# DAC_STM32_Board_v4_1_-_AD5391.net
KiCad netlist of a schematic drawn in EAGLE
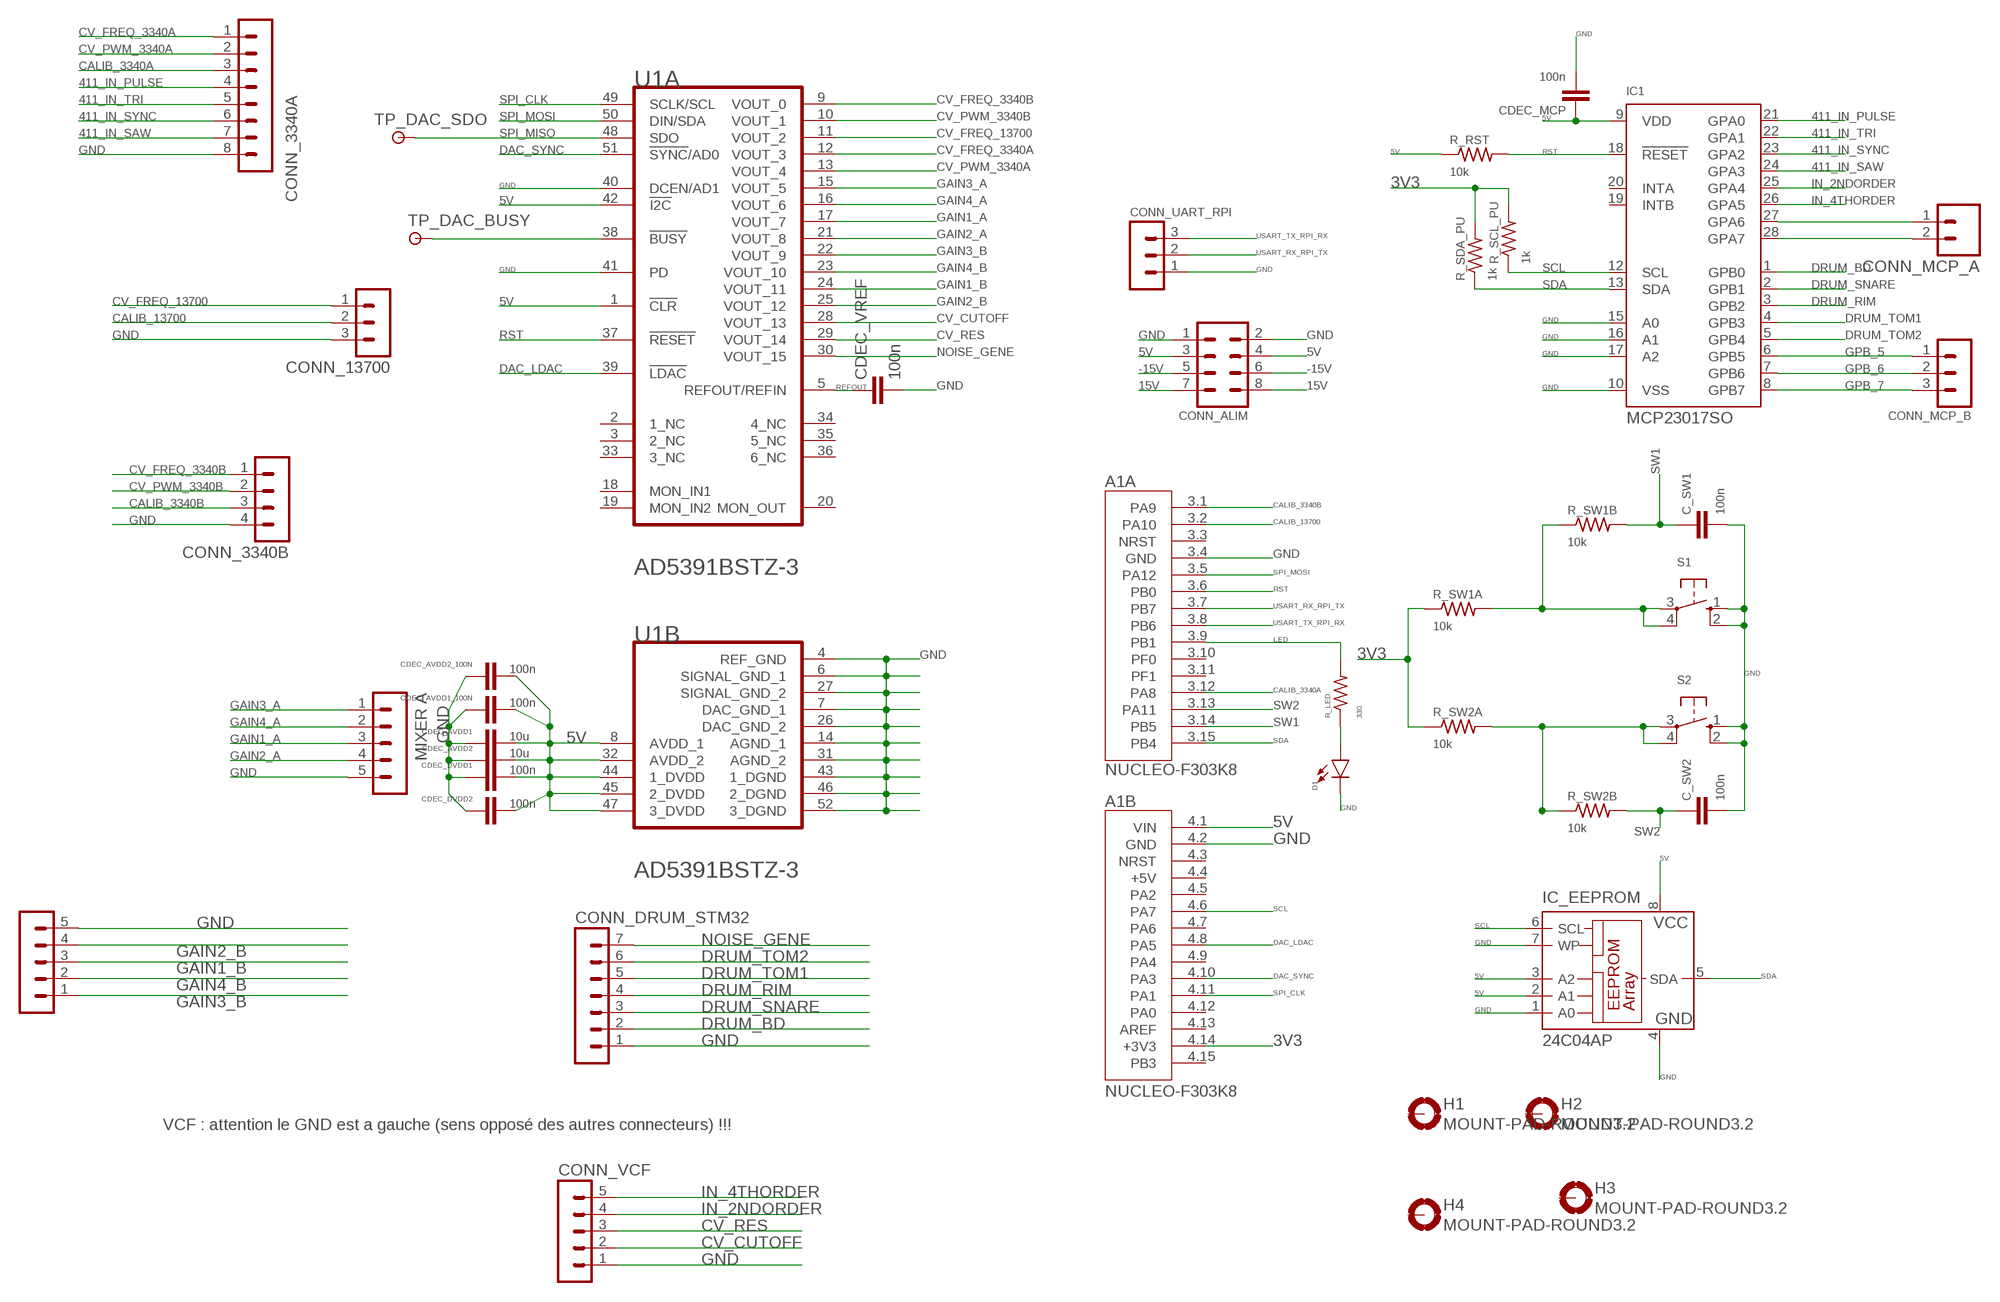
[diagram p0: schematic, sheet 1]

(export (version "E")
  (design (tool "Eeschema 10.0.6"))
  (components
    (comp (ref "A1")
      (value "NUCLEO-F303K8")
      (footprint "eagle-import:MODULE_NUCLEO-F303K8")
      (fields (field (name "DIGI-KEY_PART_NUMBER") "497-15981-ND") (field (name "MF") "STMicroelectronics"))
      (libsource (lib "eagle-import") (part "NUCLEO-F303K8"))
    )
    (comp (ref "CDEC_AVDD1")
      (value "10u")
      (footprint "eagle-import:C050-030X075")
      (libsource (lib "eagle-import") (part "C-EU050-030X075"))
    )
    (comp (ref "CDEC_AVDD1_100N")
      (value "100n")
      (footprint "eagle-import:C050-030X075")
      (libsource (lib "eagle-import") (part "C-EU050-030X075"))
    )
    (comp (ref "CDEC_AVDD2")
      (value "10u")
      (footprint "eagle-import:C050-030X075")
      (libsource (lib "eagle-import") (part "C-EU050-030X075"))
    )
    (comp (ref "CDEC_AVDD2_100N")
      (value "100n")
      (footprint "eagle-import:C050-030X075")
      (libsource (lib "eagle-import") (part "C-EU050-030X075"))
    )
    (comp (ref "CDEC_DVDD1")
      (value "100n")
      (footprint "eagle-import:C075-032X103")
      (libsource (lib "eagle-import") (part "C-EU075-032X103"))
    )
    (comp (ref "CDEC_DVDD2")
      (value "100n")
      (footprint "eagle-import:C050-030X075")
      (libsource (lib "eagle-import") (part "C-EU050-030X075"))
    )
    (comp (ref "CDEC_MCP")
      (value "100n")
      (footprint "eagle-import:C075-032X103")
      (libsource (lib "eagle-import") (part "C-EU075-032X103"))
    )
    (comp (ref "CDEC_VREF")
      (value "100n")
      (footprint "eagle-import:C050-030X075")
      (libsource (lib "eagle-import") (part "C-EU050-030X075"))
    )
    (comp (ref "CONN_3340A")
      (value "MA08-1")
      (footprint "eagle-import:MA08-1")
      (libsource (lib "eagle-import") (part "MA08-1"))
    )
    (comp (ref "CONN_3340B")
      (value "MA04-1")
      (footprint "eagle-import:MA04-1")
      (libsource (lib "eagle-import") (part "MA04-1"))
    )
    (comp (ref "CONN_13700")
      (value "MA03-1")
      (footprint "eagle-import:MA03-1")
      (libsource (lib "eagle-import") (part "MA03-1"))
    )
    (comp (ref "CONN_ALIM")
      (value "MA04-2")
      (footprint "eagle-import:MA04-2")
      (libsource (lib "eagle-import") (part "MA04-2"))
    )
    (comp (ref "CONN_DRUM_STM32")
      (value "MA07-1")
      (footprint "eagle-import:MA07-1")
      (libsource (lib "eagle-import") (part "MA07-1"))
    )
    (comp (ref "CONN_MCP_A")
      (value "M02")
      (footprint "eagle-import:02P")
      (libsource (lib "eagle-import") (part "M02"))
    )
    (comp (ref "CONN_MCP_B")
      (value "MA03-1")
      (footprint "eagle-import:MA03-1")
      (libsource (lib "eagle-import") (part "MA03-1"))
    )
    (comp (ref "CONN_MIX_A")
      (value "MA05-1")
      (footprint "eagle-import:MA05-1")
      (libsource (lib "eagle-import") (part "MA05-1"))
    )
    (comp (ref "CONN_MIX_B")
      (value "MA05-1")
      (footprint "eagle-import:MA05-1")
      (libsource (lib "eagle-import") (part "MA05-1"))
    )
    (comp (ref "CONN_UART_RPI")
      (value "MA03-1")
      (footprint "eagle-import:MA03-1")
      (libsource (lib "eagle-import") (part "MA03-1"))
    )
    (comp (ref "CONN_VCF")
      (value "MA05-1")
      (footprint "eagle-import:MA05-1")
      (libsource (lib "eagle-import") (part "MA05-1"))
    )
    (comp (ref "C_SW1")
      (value "100n")
      (footprint "eagle-import:C050-030X075")
      (libsource (lib "eagle-import") (part "C-EU050-030X075"))
    )
    (comp (ref "C_SW2")
      (value "100n")
      (footprint "eagle-import:C050-030X075")
      (libsource (lib "eagle-import") (part "C-EU050-030X075"))
    )
    (comp (ref "D1")
      (value "LED-3MM-NO_SILK")
      (footprint "eagle-import:LED_3MM-NS")
      (libsource (lib "eagle-import") (part "LED-3MM-NO_SILK"))
    )
    (comp (ref "H1")
      (value "MOUNT-PAD-ROUND3.2")
      (footprint "eagle-import:3,2-PAD")
      (libsource (lib "eagle-import") (part "MOUNT-PAD-ROUND3.2"))
    )
    (comp (ref "H2")
      (value "MOUNT-PAD-ROUND3.2")
      (footprint "eagle-import:3,2-PAD")
      (libsource (lib "eagle-import") (part "MOUNT-PAD-ROUND3.2"))
    )
    (comp (ref "H3")
      (value "MOUNT-PAD-ROUND3.2")
      (footprint "eagle-import:3,2-PAD")
      (libsource (lib "eagle-import") (part "MOUNT-PAD-ROUND3.2"))
    )
    (comp (ref "H4")
      (value "MOUNT-PAD-ROUND3.2")
      (footprint "eagle-import:3,2-PAD")
      (libsource (lib "eagle-import") (part "MOUNT-PAD-ROUND3.2"))
    )
    (comp (ref "IC1")
      (value "MCP23017SO")
      (footprint "eagle-import:SO28W")
      (fields (field (name "MF") "MICROCHIP") (field (name "MPN") "MCP23017-E/SO"))
      (libsource (lib "eagle-import") (part "MCP23017SO"))
    )
    (comp (ref "IC_EEPROM")
      (value "24C04AP")
      (footprint "eagle-import:DIL8")
      (fields (field (name "MPN") "AT24C04B-PU"))
      (libsource (lib "eagle-import") (part "24CP04A"))
    )
    (comp (ref "R_LED")
      (value "330")
      (footprint "eagle-import:0204_7")
      (libsource (lib "eagle-import") (part "R-US_0204/7"))
    )
    (comp (ref "R_RST")
      (value "10k")
      (footprint "eagle-import:0207_10")
      (libsource (lib "eagle-import") (part "R-US_0207/10"))
    )
    (comp (ref "R_SCL_PU")
      (value "1k")
      (footprint "eagle-import:0207_10")
      (libsource (lib "eagle-import") (part "R-US_0207/10"))
    )
    (comp (ref "R_SDA_PU")
      (value "1k")
      (footprint "eagle-import:0207_10")
      (libsource (lib "eagle-import") (part "R-US_0207/10"))
    )
    (comp (ref "R_SW1A")
      (value "10k")
      (footprint "eagle-import:0207_10")
      (libsource (lib "eagle-import") (part "R-US_0207/10"))
    )
    (comp (ref "R_SW1B")
      (value "10k")
      (footprint "eagle-import:0207_10")
      (libsource (lib "eagle-import") (part "R-US_0207/10"))
    )
    (comp (ref "R_SW2A")
      (value "10k")
      (footprint "eagle-import:0207_10")
      (libsource (lib "eagle-import") (part "R-US_0207/10"))
    )
    (comp (ref "R_SW2B")
      (value "10k")
      (footprint "eagle-import:0207_10")
      (libsource (lib "eagle-import") (part "R-US_0207/10"))
    )
    (comp (ref "S1")
      (value "10-XX")
      (footprint "eagle-import:B3F-10XX")
      (fields (field (name "MPN") "B3F-1000"))
      (libsource (lib "eagle-import") (part "10-XX"))
    )
    (comp (ref "S2")
      (value "10-XX")
      (footprint "eagle-import:B3F-10XX")
      (fields (field (name "MPN") "B3F-1000"))
      (libsource (lib "eagle-import") (part "10-XX"))
    )
    (comp (ref "TP_DAC_BUSY")
      (value "PAD-TESTPOINT")
      (footprint "eagle-import:1,6_0,8")
      (libsource (lib "eagle-import") (part "PAD-TESTPOINT"))
    )
    (comp (ref "TP_DAC_SDO")
      (value "PAD-TESTPOINT")
      (footprint "eagle-import:1,6_0,8")
      (libsource (lib "eagle-import") (part "PAD-TESTPOINT"))
    )
    (comp (ref "U1")
      (value "ANALOG_DEVICES_AD5391BSTZ-3ANALOG_DEVICES_AD5391BSTZ-3_0_0")
      (footprint "eagle-import:ANALOG_DEVICES_AD5391BSTZ-3_0")
      (fields (field (name "MF") "Analog Devices") (field (name "MPN") "AD5391BSTZ-3"))
      (libsource (lib "eagle-import") (part "ANALOG_DEVICES_AD5391BSTZ-3ANALOG_DEVICES_AD5391BSTZ-3_0_0"))
    )
  )
  (nets
    (net (code "1") (name "/-15V") (class "Default")
      (node (ref "CONN_ALIM") (pin "5") (pinfunction "5_5") (pintype "passive"))
      (node (ref "CONN_ALIM") (pin "6") (pinfunction "6_6") (pintype "passive"))
    )
    (net (code "2") (name "/3V3") (class "Default")
      (node (ref "A1") (pin "4.14") (pinfunction "+3V3_4.14") (pintype "bidirectional"))
      (node (ref "R_SCL_PU") (pin "2") (pinfunction "2_2") (pintype "passive"))
      (node (ref "R_SDA_PU") (pin "2") (pinfunction "2_2") (pintype "passive"))
      (node (ref "R_SW1A") (pin "1") (pinfunction "1_1") (pintype "passive"))
      (node (ref "R_SW2A") (pin "1") (pinfunction "1_1") (pintype "passive"))
    )
    (net (code "3") (name "/5V") (class "Default")
      (node (ref "A1") (pin "4.1") (pinfunction "VIN_4.1") (pintype "bidirectional"))
      (node (ref "CDEC_AVDD1") (pin "2") (pinfunction "2_2") (pintype "passive"))
      (node (ref "CDEC_AVDD1_100N") (pin "2") (pinfunction "2_2") (pintype "passive"))
      (node (ref "CDEC_AVDD2") (pin "2") (pinfunction "2_2") (pintype "passive"))
      (node (ref "CDEC_AVDD2_100N") (pin "2") (pinfunction "2_2") (pintype "passive"))
      (node (ref "CDEC_DVDD1") (pin "2") (pinfunction "2_2") (pintype "passive"))
      (node (ref "CDEC_DVDD2") (pin "2") (pinfunction "2_2") (pintype "passive"))
      (node (ref "CDEC_MCP") (pin "1") (pinfunction "1_1") (pintype "passive"))
      (node (ref "CONN_ALIM") (pin "3") (pinfunction "3_3") (pintype "passive"))
      (node (ref "CONN_ALIM") (pin "4") (pinfunction "4_4") (pintype "passive"))
      (node (ref "IC1") (pin "9") (pinfunction "VDD_9") (pintype "power_in"))
      (node (ref "IC_EEPROM") (pin "2") (pinfunction "A1_2") (pintype "input"))
      (node (ref "IC_EEPROM") (pin "3") (pinfunction "A2_3") (pintype "input"))
      (node (ref "IC_EEPROM") (pin "8") (pinfunction "VCC_8") (pintype "power_in"))
      (node (ref "R_RST") (pin "1") (pinfunction "1_1") (pintype "passive"))
      (node (ref "U1") (pin "1") (pinfunction "~{CLR}_1") (pintype "input"))
      (node (ref "U1") (pin "32") (pinfunction "AVDD_2_32") (pintype "power_in"))
      (node (ref "U1") (pin "42") (pinfunction "~{I2C}_42") (pintype "input"))
      (node (ref "U1") (pin "44") (pinfunction "1_DVDD_44") (pintype "power_in"))
      (node (ref "U1") (pin "45") (pinfunction "2_DVDD_45") (pintype "power_in"))
      (node (ref "U1") (pin "47") (pinfunction "3_DVDD_47") (pintype "power_in"))
      (node (ref "U1") (pin "8") (pinfunction "AVDD_1_8") (pintype "power_in"))
    )
    (net (code "4") (name "/15V") (class "Default")
      (node (ref "CONN_ALIM") (pin "7") (pinfunction "7_7") (pintype "passive"))
      (node (ref "CONN_ALIM") (pin "8") (pinfunction "8_8") (pintype "passive"))
    )
    (net (code "5") (name "/411_IN_PULSE") (class "Default")
      (node (ref "CONN_3340A") (pin "4") (pinfunction "4_4") (pintype "passive"))
      (node (ref "IC1") (pin "21") (pinfunction "GPA0_21") (pintype "bidirectional"))
    )
    (net (code "6") (name "/411_IN_SAW") (class "Default")
      (node (ref "CONN_3340A") (pin "7") (pinfunction "7_7") (pintype "passive"))
      (node (ref "IC1") (pin "24") (pinfunction "GPA3_24") (pintype "bidirectional"))
    )
    (net (code "7") (name "/411_IN_SYNC") (class "Default")
      (node (ref "CONN_3340A") (pin "6") (pinfunction "6_6") (pintype "passive"))
      (node (ref "IC1") (pin "23") (pinfunction "GPA2_23") (pintype "bidirectional"))
    )
    (net (code "8") (name "/411_IN_TRI") (class "Default")
      (node (ref "CONN_3340A") (pin "5") (pinfunction "5_5") (pintype "passive"))
      (node (ref "IC1") (pin "22") (pinfunction "GPA1_22") (pintype "bidirectional"))
    )
    (net (code "9") (name "/CALIB_3340A") (class "Default")
      (node (ref "A1") (pin "3.12") (pinfunction "PA8_3.12") (pintype "bidirectional"))
      (node (ref "CONN_3340A") (pin "3") (pinfunction "3_3") (pintype "passive"))
    )
    (net (code "10") (name "/CALIB_3340B") (class "Default")
      (node (ref "A1") (pin "3.1") (pinfunction "PA9_3.1") (pintype "bidirectional"))
      (node (ref "CONN_3340B") (pin "3") (pinfunction "3_3") (pintype "passive"))
    )
    (net (code "11") (name "/CALIB_13700") (class "Default")
      (node (ref "A1") (pin "3.2") (pinfunction "PA10_3.2") (pintype "bidirectional"))
      (node (ref "CONN_13700") (pin "2") (pinfunction "2_2") (pintype "passive"))
    )
    (net (code "12") (name "/CV_CUTOFF") (class "Default")
      (node (ref "CONN_VCF") (pin "2") (pinfunction "2_2") (pintype "passive"))
      (node (ref "U1") (pin "28") (pinfunction "VOUT_13_28") (pintype "tri_state"))
    )
    (net (code "13") (name "/CV_FREQ_3340A") (class "Default")
      (node (ref "CONN_3340A") (pin "1") (pinfunction "1_1") (pintype "passive"))
      (node (ref "U1") (pin "12") (pinfunction "VOUT_3_12") (pintype "tri_state"))
    )
    (net (code "14") (name "/CV_FREQ_3340B") (class "Default")
      (node (ref "CONN_3340B") (pin "1") (pinfunction "1_1") (pintype "passive"))
      (node (ref "U1") (pin "9") (pinfunction "VOUT_0_9") (pintype "tri_state"))
    )
    (net (code "15") (name "/CV_FREQ_13700") (class "Default")
      (node (ref "CONN_13700") (pin "1") (pinfunction "1_1") (pintype "passive"))
      (node (ref "U1") (pin "11") (pinfunction "VOUT_2_11") (pintype "tri_state"))
    )
    (net (code "16") (name "/CV_PWM_3340A") (class "Default")
      (node (ref "CONN_3340A") (pin "2") (pinfunction "2_2") (pintype "passive"))
      (node (ref "U1") (pin "13") (pinfunction "VOUT_4_13") (pintype "tri_state"))
    )
    (net (code "17") (name "/CV_PWM_3340B") (class "Default")
      (node (ref "CONN_3340B") (pin "2") (pinfunction "2_2") (pintype "passive"))
      (node (ref "U1") (pin "10") (pinfunction "VOUT_1_10") (pintype "tri_state"))
    )
    (net (code "18") (name "/CV_RES") (class "Default")
      (node (ref "CONN_VCF") (pin "3") (pinfunction "3_3") (pintype "passive"))
      (node (ref "U1") (pin "29") (pinfunction "VOUT_14_29") (pintype "tri_state"))
    )
    (net (code "19") (name "/DAC_LDAC") (class "Default")
      (node (ref "A1") (pin "4.8") (pinfunction "PA5_4.8") (pintype "bidirectional"))
      (node (ref "U1") (pin "39") (pinfunction "~{LDAC}_39") (pintype "input"))
    )
    (net (code "20") (name "/DAC_SYNC") (class "Default")
      (node (ref "A1") (pin "4.10") (pinfunction "PA3_4.10") (pintype "bidirectional"))
      (node (ref "U1") (pin "51") (pinfunction "~{SYNC}/AD0_51") (pintype "input"))
    )
    (net (code "21") (name "/DRUM_BD") (class "Default")
      (node (ref "CONN_DRUM_STM32") (pin "2") (pinfunction "2_2") (pintype "passive"))
      (node (ref "IC1") (pin "1") (pinfunction "GPB0_1") (pintype "bidirectional"))
    )
    (net (code "22") (name "/DRUM_RIM") (class "Default")
      (node (ref "CONN_DRUM_STM32") (pin "4") (pinfunction "4_4") (pintype "passive"))
      (node (ref "IC1") (pin "3") (pinfunction "GPB2_3") (pintype "bidirectional"))
    )
    (net (code "23") (name "/DRUM_SNARE") (class "Default")
      (node (ref "CONN_DRUM_STM32") (pin "3") (pinfunction "3_3") (pintype "passive"))
      (node (ref "IC1") (pin "2") (pinfunction "GPB1_2") (pintype "bidirectional"))
    )
    (net (code "24") (name "/DRUM_TOM1") (class "Default")
      (node (ref "CONN_DRUM_STM32") (pin "5") (pinfunction "5_5") (pintype "passive"))
      (node (ref "IC1") (pin "4") (pinfunction "GPB3_4") (pintype "bidirectional"))
    )
    (net (code "25") (name "/DRUM_TOM2") (class "Default")
      (node (ref "CONN_DRUM_STM32") (pin "6") (pinfunction "6_6") (pintype "passive"))
      (node (ref "IC1") (pin "5") (pinfunction "GPB4_5") (pintype "bidirectional"))
    )
    (net (code "26") (name "/GAIN1_A") (class "Default")
      (node (ref "CONN_MIX_A") (pin "3") (pinfunction "3_3") (pintype "passive"))
      (node (ref "U1") (pin "17") (pinfunction "VOUT_7_17") (pintype "tri_state"))
    )
    (net (code "27") (name "/GAIN1_B") (class "Default")
      (node (ref "CONN_MIX_B") (pin "3") (pinfunction "3_3") (pintype "passive"))
      (node (ref "U1") (pin "24") (pinfunction "VOUT_11_24") (pintype "tri_state"))
    )
    (net (code "28") (name "/GAIN2_A") (class "Default")
      (node (ref "CONN_MIX_A") (pin "4") (pinfunction "4_4") (pintype "passive"))
      (node (ref "U1") (pin "21") (pinfunction "VOUT_8_21") (pintype "tri_state"))
    )
    (net (code "29") (name "/GAIN2_B") (class "Default")
      (node (ref "CONN_MIX_B") (pin "4") (pinfunction "4_4") (pintype "passive"))
      (node (ref "U1") (pin "25") (pinfunction "VOUT_12_25") (pintype "tri_state"))
    )
    (net (code "30") (name "/GAIN3_A") (class "Default")
      (node (ref "CONN_MIX_A") (pin "1") (pinfunction "1_1") (pintype "passive"))
      (node (ref "U1") (pin "15") (pinfunction "VOUT_5_15") (pintype "tri_state"))
    )
    (net (code "31") (name "/GAIN3_B") (class "Default")
      (node (ref "CONN_MIX_B") (pin "1") (pinfunction "1_1") (pintype "passive"))
      (node (ref "U1") (pin "22") (pinfunction "VOUT_9_22") (pintype "tri_state"))
    )
    (net (code "32") (name "/GAIN4_A") (class "Default")
      (node (ref "CONN_MIX_A") (pin "2") (pinfunction "2_2") (pintype "passive"))
      (node (ref "U1") (pin "16") (pinfunction "VOUT_6_16") (pintype "tri_state"))
    )
    (net (code "33") (name "/GAIN4_B") (class "Default")
      (node (ref "CONN_MIX_B") (pin "2") (pinfunction "2_2") (pintype "passive"))
      (node (ref "U1") (pin "23") (pinfunction "VOUT_10_23") (pintype "tri_state"))
    )
    (net (code "34") (name "/GND") (class "Default")
      (node (ref "A1") (pin "3.4") (pinfunction "GND_3.4") (pintype "bidirectional"))
      (node (ref "A1") (pin "4.2") (pinfunction "GND_4.2") (pintype "bidirectional"))
      (node (ref "CDEC_AVDD1") (pin "1") (pinfunction "1_1") (pintype "passive"))
      (node (ref "CDEC_AVDD1_100N") (pin "1") (pinfunction "1_1") (pintype "passive"))
      (node (ref "CDEC_AVDD2") (pin "1") (pinfunction "1_1") (pintype "passive"))
      (node (ref "CDEC_AVDD2_100N") (pin "1") (pinfunction "1_1") (pintype "passive"))
      (node (ref "CDEC_DVDD1") (pin "1") (pinfunction "1_1") (pintype "passive"))
      (node (ref "CDEC_DVDD2") (pin "1") (pinfunction "1_1") (pintype "passive"))
      (node (ref "CDEC_MCP") (pin "2") (pinfunction "2_2") (pintype "passive"))
      (node (ref "CDEC_VREF") (pin "2") (pinfunction "2_2") (pintype "passive"))
      (node (ref "CONN_13700") (pin "3") (pinfunction "3_3") (pintype "passive"))
      (node (ref "CONN_3340A") (pin "8") (pinfunction "8_8") (pintype "passive"))
      (node (ref "CONN_3340B") (pin "4") (pinfunction "4_4") (pintype "passive"))
      (node (ref "CONN_ALIM") (pin "1") (pinfunction "1_1") (pintype "passive"))
      (node (ref "CONN_ALIM") (pin "2") (pinfunction "2_2") (pintype "passive"))
      (node (ref "CONN_DRUM_STM32") (pin "1") (pinfunction "1_1") (pintype "passive"))
      (node (ref "CONN_MIX_A") (pin "5") (pinfunction "5_5") (pintype "passive"))
      (node (ref "CONN_MIX_B") (pin "5") (pinfunction "5_5") (pintype "passive"))
      (node (ref "CONN_UART_RPI") (pin "1") (pinfunction "1_1") (pintype "passive"))
      (node (ref "CONN_VCF") (pin "1") (pinfunction "1_1") (pintype "passive"))
      (node (ref "C_SW1") (pin "2") (pinfunction "2_2") (pintype "passive"))
      (node (ref "C_SW2") (pin "2") (pinfunction "2_2") (pintype "passive"))
      (node (ref "D1") (pin "K") (pinfunction "C_K") (pintype "passive"))
      (node (ref "IC1") (pin "10") (pinfunction "VSS_10") (pintype "power_in"))
      (node (ref "IC1") (pin "15") (pinfunction "A0_15") (pintype "input"))
      (node (ref "IC1") (pin "16") (pinfunction "A1_16") (pintype "input"))
      (node (ref "IC1") (pin "17") (pinfunction "A2_17") (pintype "input"))
      (node (ref "IC_EEPROM") (pin "1") (pinfunction "A0_1") (pintype "input"))
      (node (ref "IC_EEPROM") (pin "4") (pinfunction "GND_4") (pintype "power_in"))
      (node (ref "IC_EEPROM") (pin "7") (pinfunction "WP_7") (pintype "input"))
      (node (ref "S1") (pin "1") (pinfunction "S_1") (pintype "passive"))
      (node (ref "S1") (pin "2") (pinfunction "S1_2") (pintype "passive"))
      (node (ref "S2") (pin "1") (pinfunction "S_1") (pintype "passive"))
      (node (ref "S2") (pin "2") (pinfunction "S1_2") (pintype "passive"))
      (node (ref "U1") (pin "14") (pinfunction "AGND_1_14") (pintype "power_in"))
      (node (ref "U1") (pin "26") (pinfunction "DAC_GND_2_26") (pintype "power_in"))
      (node (ref "U1") (pin "27") (pinfunction "SIGNAL_GND_2_27") (pintype "power_in"))
      (node (ref "U1") (pin "31") (pinfunction "AGND_2_31") (pintype "power_in"))
      (node (ref "U1") (pin "4") (pinfunction "REF_GND_4") (pintype "power_in"))
      (node (ref "U1") (pin "40") (pinfunction "DCEN/AD1_40") (pintype "input"))
      (node (ref "U1") (pin "41") (pinfunction "PD_41") (pintype "input"))
      (node (ref "U1") (pin "43") (pinfunction "1_DGND_43") (pintype "power_in"))
      (node (ref "U1") (pin "46") (pinfunction "2_DGND_46") (pintype "power_in"))
      (node (ref "U1") (pin "52") (pinfunction "3_DGND_52") (pintype "power_in"))
      (node (ref "U1") (pin "6") (pinfunction "SIGNAL_GND_1_6") (pintype "power_in"))
      (node (ref "U1") (pin "7") (pinfunction "DAC_GND_1_7") (pintype "power_in"))
    )
    (net (code "35") (name "/GPB_5") (class "Default")
      (node (ref "CONN_MCP_B") (pin "1") (pinfunction "1_1") (pintype "passive"))
      (node (ref "IC1") (pin "6") (pinfunction "GPB5_6") (pintype "bidirectional"))
    )
    (net (code "36") (name "/GPB_6") (class "Default")
      (node (ref "CONN_MCP_B") (pin "2") (pinfunction "2_2") (pintype "passive"))
      (node (ref "IC1") (pin "7") (pinfunction "GPB6_7") (pintype "bidirectional"))
    )
    (net (code "37") (name "/GPB_7") (class "Default")
      (node (ref "CONN_MCP_B") (pin "3") (pinfunction "3_3") (pintype "passive"))
      (node (ref "IC1") (pin "8") (pinfunction "GPB7_8") (pintype "bidirectional"))
    )
    (net (code "38") (name "/IN_2NDORDER") (class "Default")
      (node (ref "CONN_VCF") (pin "4") (pinfunction "4_4") (pintype "passive"))
      (node (ref "IC1") (pin "25") (pinfunction "GPA4_25") (pintype "bidirectional"))
    )
    (net (code "39") (name "/IN_4THORDER") (class "Default")
      (node (ref "CONN_VCF") (pin "5") (pinfunction "5_5") (pintype "passive"))
      (node (ref "IC1") (pin "26") (pinfunction "GPA5_26") (pintype "bidirectional"))
    )
    (net (code "40") (name "/LED") (class "Default")
      (node (ref "A1") (pin "3.9") (pinfunction "PB1_3.9") (pintype "bidirectional"))
      (node (ref "R_LED") (pin "2") (pinfunction "2_2") (pintype "passive"))
    )
    (net (code "41") (name "/NOISE_GENE") (class "Default")
      (node (ref "CONN_DRUM_STM32") (pin "7") (pinfunction "7_7") (pintype "passive"))
      (node (ref "U1") (pin "30") (pinfunction "VOUT_15_30") (pintype "tri_state"))
    )
    (net (code "42") (name "/REFOUT") (class "Default")
      (node (ref "CDEC_VREF") (pin "1") (pinfunction "1_1") (pintype "passive"))
      (node (ref "U1") (pin "5") (pinfunction "REFOUT/REFIN_5") (pintype "bidirectional"))
    )
    (net (code "43") (name "/RST") (class "Default")
      (node (ref "A1") (pin "3.6") (pinfunction "PB0_3.6") (pintype "bidirectional"))
      (node (ref "IC1") (pin "18") (pinfunction "~{RESET}_18") (pintype "input"))
      (node (ref "R_RST") (pin "2") (pinfunction "2_2") (pintype "passive"))
      (node (ref "U1") (pin "37") (pinfunction "~{RESET}_37") (pintype "input"))
    )
    (net (code "44") (name "/SCL") (class "Default")
      (node (ref "A1") (pin "4.6") (pinfunction "PA7_4.6") (pintype "bidirectional"))
      (node (ref "IC1") (pin "12") (pinfunction "SCL_12") (pintype "input"))
      (node (ref "IC_EEPROM") (pin "6") (pinfunction "SCL_6") (pintype "input"))
      (node (ref "R_SCL_PU") (pin "1") (pinfunction "1_1") (pintype "passive"))
    )
    (net (code "45") (name "/SDA") (class "Default")
      (node (ref "A1") (pin "3.15") (pinfunction "PB4_3.15") (pintype "bidirectional"))
      (node (ref "IC1") (pin "13") (pinfunction "SDA_13") (pintype "bidirectional"))
      (node (ref "IC_EEPROM") (pin "5") (pinfunction "SDA_5") (pintype "bidirectional"))
      (node (ref "R_SDA_PU") (pin "1") (pinfunction "1_1") (pintype "passive"))
    )
    (net (code "46") (name "/SPI_CLK") (class "Default")
      (node (ref "A1") (pin "4.11") (pinfunction "PA1_4.11") (pintype "bidirectional"))
      (node (ref "U1") (pin "49") (pinfunction "SCLK/SCL_49") (pintype "input"))
    )
    (net (code "47") (name "/SPI_MISO") (class "Default")
      (node (ref "TP_DAC_SDO") (pin "1") (pinfunction "P_1") (pintype "passive"))
      (node (ref "U1") (pin "48") (pinfunction "SDO_48") (pintype "tri_state"))
    )
    (net (code "48") (name "/SPI_MOSI") (class "Default")
      (node (ref "A1") (pin "3.5") (pinfunction "PA12_3.5") (pintype "bidirectional"))
      (node (ref "U1") (pin "50") (pinfunction "DIN/SDA_50") (pintype "bidirectional"))
    )
    (net (code "49") (name "/SW1") (class "Default")
      (node (ref "A1") (pin "3.14") (pinfunction "PB5_3.14") (pintype "bidirectional"))
      (node (ref "C_SW1") (pin "1") (pinfunction "1_1") (pintype "passive"))
      (node (ref "R_SW1B") (pin "2") (pinfunction "2_2") (pintype "passive"))
    )
    (net (code "50") (name "/SW2") (class "Default")
      (node (ref "A1") (pin "3.13") (pinfunction "PA11_3.13") (pintype "bidirectional"))
      (node (ref "C_SW2") (pin "1") (pinfunction "1_1") (pintype "passive"))
      (node (ref "R_SW2B") (pin "2") (pinfunction "2_2") (pintype "passive"))
    )
    (net (code "51") (name "/USART_RX_RPI_TX") (class "Default")
      (node (ref "A1") (pin "3.7") (pinfunction "PB7_3.7") (pintype "bidirectional"))
      (node (ref "CONN_UART_RPI") (pin "2") (pinfunction "2_2") (pintype "passive"))
    )
    (net (code "52") (name "/USART_TX_RPI_RX") (class "Default")
      (node (ref "A1") (pin "3.8") (pinfunction "PB6_3.8") (pintype "bidirectional"))
      (node (ref "CONN_UART_RPI") (pin "3") (pinfunction "3_3") (pintype "passive"))
    )
    (net (code "53") (name "Net-(D1-PadA)") (class "Default")
      (node (ref "D1") (pin "A") (pinfunction "A_A") (pintype "passive"))
      (node (ref "R_LED") (pin "1") (pinfunction "1_1") (pintype "passive"))
    )
    (net (code "54") (name "Net-(IC1-GPA6)") (class "Default")
      (node (ref "CONN_MCP_A") (pin "1") (pinfunction "1_1") (pintype "passive"))
      (node (ref "IC1") (pin "27") (pinfunction "GPA6_27") (pintype "bidirectional"))
    )
    (net (code "55") (name "Net-(IC1-GPA7)") (class "Default")
      (node (ref "CONN_MCP_A") (pin "2") (pinfunction "2_2") (pintype "passive"))
      (node (ref "IC1") (pin "28") (pinfunction "GPA7_28") (pintype "bidirectional"))
    )
    (net (code "56") (name "Net-(S1-P)") (class "Default")
      (node (ref "R_SW1A") (pin "2") (pinfunction "2_2") (pintype "passive"))
      (node (ref "R_SW1B") (pin "1") (pinfunction "1_1") (pintype "passive"))
      (node (ref "S1") (pin "3") (pinfunction "P_3") (pintype "passive"))
      (node (ref "S1") (pin "4") (pinfunction "P1_4") (pintype "passive"))
    )
    (net (code "57") (name "Net-(S2-P)") (class "Default")
      (node (ref "R_SW2A") (pin "2") (pinfunction "2_2") (pintype "passive"))
      (node (ref "R_SW2B") (pin "1") (pinfunction "1_1") (pintype "passive"))
      (node (ref "S2") (pin "3") (pinfunction "P_3") (pintype "passive"))
      (node (ref "S2") (pin "4") (pinfunction "P1_4") (pintype "passive"))
    )
    (net (code "58") (name "Net-(TP_DAC_BUSY-P)") (class "Default")
      (node (ref "TP_DAC_BUSY") (pin "1") (pinfunction "P_1") (pintype "passive"))
      (node (ref "U1") (pin "38") (pinfunction "~{BUSY}_38") (pintype "output"))
    )
    (net (code "59") (name "unconnected-(A1A-NRST-Pad3.3)") (class "Default")
      (node (ref "A1") (pin "3.3") (pinfunction "NRST_3.3") (pintype "bidirectional"))
    )
    (net (code "60") (name "unconnected-(A1A-PF0-Pad3.10)") (class "Default")
      (node (ref "A1") (pin "3.10") (pinfunction "PF0_3.10") (pintype "bidirectional"))
    )
    (net (code "61") (name "unconnected-(A1A-PF1-Pad3.11)") (class "Default")
      (node (ref "A1") (pin "3.11") (pinfunction "PF1_3.11") (pintype "bidirectional"))
    )
    (net (code "62") (name "unconnected-(A1B-+5V-Pad4.4)") (class "Default")
      (node (ref "A1") (pin "4.4") (pinfunction "+5V_4.4") (pintype "bidirectional"))
    )
    (net (code "63") (name "unconnected-(A1B-AREF-Pad4.13)") (class "Default")
      (node (ref "A1") (pin "4.13") (pinfunction "AREF_4.13") (pintype "bidirectional"))
    )
    (net (code "64") (name "unconnected-(A1B-NRST-Pad4.3)") (class "Default")
      (node (ref "A1") (pin "4.3") (pinfunction "NRST_4.3") (pintype "bidirectional"))
    )
    (net (code "65") (name "unconnected-(A1B-PA0-Pad4.12)") (class "Default")
      (node (ref "A1") (pin "4.12") (pinfunction "PA0_4.12") (pintype "bidirectional"))
    )
    (net (code "66") (name "unconnected-(A1B-PA2-Pad4.5)") (class "Default")
      (node (ref "A1") (pin "4.5") (pinfunction "PA2_4.5") (pintype "bidirectional"))
    )
    (net (code "67") (name "unconnected-(A1B-PA4-Pad4.9)") (class "Default")
      (node (ref "A1") (pin "4.9") (pinfunction "PA4_4.9") (pintype "bidirectional"))
    )
    (net (code "68") (name "unconnected-(A1B-PA6-Pad4.7)") (class "Default")
      (node (ref "A1") (pin "4.7") (pinfunction "PA6_4.7") (pintype "bidirectional"))
    )
    (net (code "69") (name "unconnected-(A1B-PB3-Pad4.15)") (class "Default")
      (node (ref "A1") (pin "4.15") (pinfunction "PB3_4.15") (pintype "bidirectional"))
    )
    (net (code "70") (name "unconnected-(H1-MOUNT-PadB3,2)") (class "Default")
      (node (ref "H1") (pin "B3,2") (pinfunction "MOUNT_B3,2") (pintype "passive"))
    )
    (net (code "71") (name "unconnected-(H2-MOUNT-PadB3,2)") (class "Default")
      (node (ref "H2") (pin "B3,2") (pinfunction "MOUNT_B3,2") (pintype "passive"))
    )
    (net (code "72") (name "unconnected-(H3-MOUNT-PadB3,2)") (class "Default")
      (node (ref "H3") (pin "B3,2") (pinfunction "MOUNT_B3,2") (pintype "passive"))
    )
    (net (code "73") (name "unconnected-(H4-MOUNT-PadB3,2)") (class "Default")
      (node (ref "H4") (pin "B3,2") (pinfunction "MOUNT_B3,2") (pintype "passive"))
    )
    (net (code "74") (name "unconnected-(IC1-INTA-Pad20)") (class "Default")
      (node (ref "IC1") (pin "20") (pinfunction "INTA_20") (pintype "output"))
    )
    (net (code "75") (name "unconnected-(IC1-INTB-Pad19)") (class "Default")
      (node (ref "IC1") (pin "19") (pinfunction "INTB_19") (pintype "output"))
    )
    (net (code "76") (name "unconnected-(U1A-1_NC-Pad2)") (class "Default")
      (node (ref "U1") (pin "2") (pinfunction "1_NC_2") (pintype "passive"))
    )
    (net (code "77") (name "unconnected-(U1A-2_NC-Pad3)") (class "Default")
      (node (ref "U1") (pin "3") (pinfunction "2_NC_3") (pintype "passive"))
    )
    (net (code "78") (name "unconnected-(U1A-3_NC-Pad33)") (class "Default")
      (node (ref "U1") (pin "33") (pinfunction "3_NC_33") (pintype "passive"))
    )
    (net (code "79") (name "unconnected-(U1A-4_NC-Pad34)") (class "Default")
      (node (ref "U1") (pin "34") (pinfunction "4_NC_34") (pintype "passive"))
    )
    (net (code "80") (name "unconnected-(U1A-5_NC-Pad35)") (class "Default")
      (node (ref "U1") (pin "35") (pinfunction "5_NC_35") (pintype "passive"))
    )
    (net (code "81") (name "unconnected-(U1A-6_NC-Pad36)") (class "Default")
      (node (ref "U1") (pin "36") (pinfunction "6_NC_36") (pintype "passive"))
    )
    (net (code "82") (name "unconnected-(U1A-MON_IN1-Pad18)") (class "Default")
      (node (ref "U1") (pin "18") (pinfunction "MON_IN1_18") (pintype "input"))
    )
    (net (code "83") (name "unconnected-(U1A-MON_IN2-Pad19)") (class "Default")
      (node (ref "U1") (pin "19") (pinfunction "MON_IN2_19") (pintype "input"))
    )
    (net (code "84") (name "unconnected-(U1A-MON_OUT-Pad20)") (class "Default")
      (node (ref "U1") (pin "20") (pinfunction "MON_OUT_20") (pintype "tri_state"))
    )
  )
)
